# oeuf_sous_vide.net
KiCad netlist of a schematic drawn in EAGLE
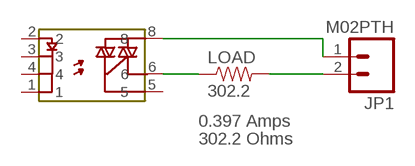
[diagram p0: schematic, sheet 1]

(export (version "E")
  (design (tool "Eeschema 10.0.6"))
  (components
    (comp (ref "JP1")
      (value "M02PTH")
      (footprint "eagle-import:1X02")
      (libsource (lib "eagle-import") (part "M02PTH"))
    )
    (comp (ref "LOAD")
      (value "302.2")
      (footprint "eagle-import:AXIAL-0.3")
      (libsource (lib "eagle-import") (part "RESISTORAXIAL-0.3"))
    )
    (comp (ref "U$1")
      (value "PR39MF5")
      (footprint "eagle-import:PR39MF51")
      (libsource (lib "eagle-import") (part "PR39MF5"))
    )
  )
  (nets
    (net (code "1") (name "Net-(JP1-Pad1)") (class "Default")
      (node (ref "JP1") (pin "1") (pinfunction "1_1") (pintype "passive"))
      (node (ref "U$1") (pin "8") (pinfunction "8_8") (pintype "output"))
    )
    (net (code "2") (name "Net-(LOAD-1)") (class "Default")
      (node (ref "LOAD") (pin "P$1") (pinfunction "1_P$1") (pintype "passive"))
      (node (ref "U$1") (pin "6") (pinfunction "6_6") (pintype "output"))
    )
    (net (code "3") (name "Net-(LOAD-2)") (class "Default")
      (node (ref "JP1") (pin "2") (pinfunction "2_2") (pintype "passive"))
      (node (ref "LOAD") (pin "P$2") (pinfunction "2_P$2") (pintype "passive"))
    )
    (net (code "4") (name "unconnected-(U$1-Pad1)") (class "Default")
      (node (ref "U$1") (pin "1") (pinfunction "1_1") (pintype "input"))
    )
    (net (code "5") (name "unconnected-(U$1-Pad2)") (class "Default")
      (node (ref "U$1") (pin "2") (pinfunction "2_2") (pintype "input"))
    )
    (net (code "6") (name "unconnected-(U$1-Pad3)") (class "Default")
      (node (ref "U$1") (pin "3") (pinfunction "3_3") (pintype "input"))
    )
    (net (code "7") (name "unconnected-(U$1-Pad4)") (class "Default")
      (node (ref "U$1") (pin "4") (pinfunction "4_4") (pintype "input"))
    )
    (net (code "8") (name "unconnected-(U$1-Pad5)") (class "Default")
      (node (ref "U$1") (pin "5") (pinfunction "5_5") (pintype "no_connect"))
    )
  )
)
